# aspirin.net
KiCad netlist of a schematic drawn in EAGLE
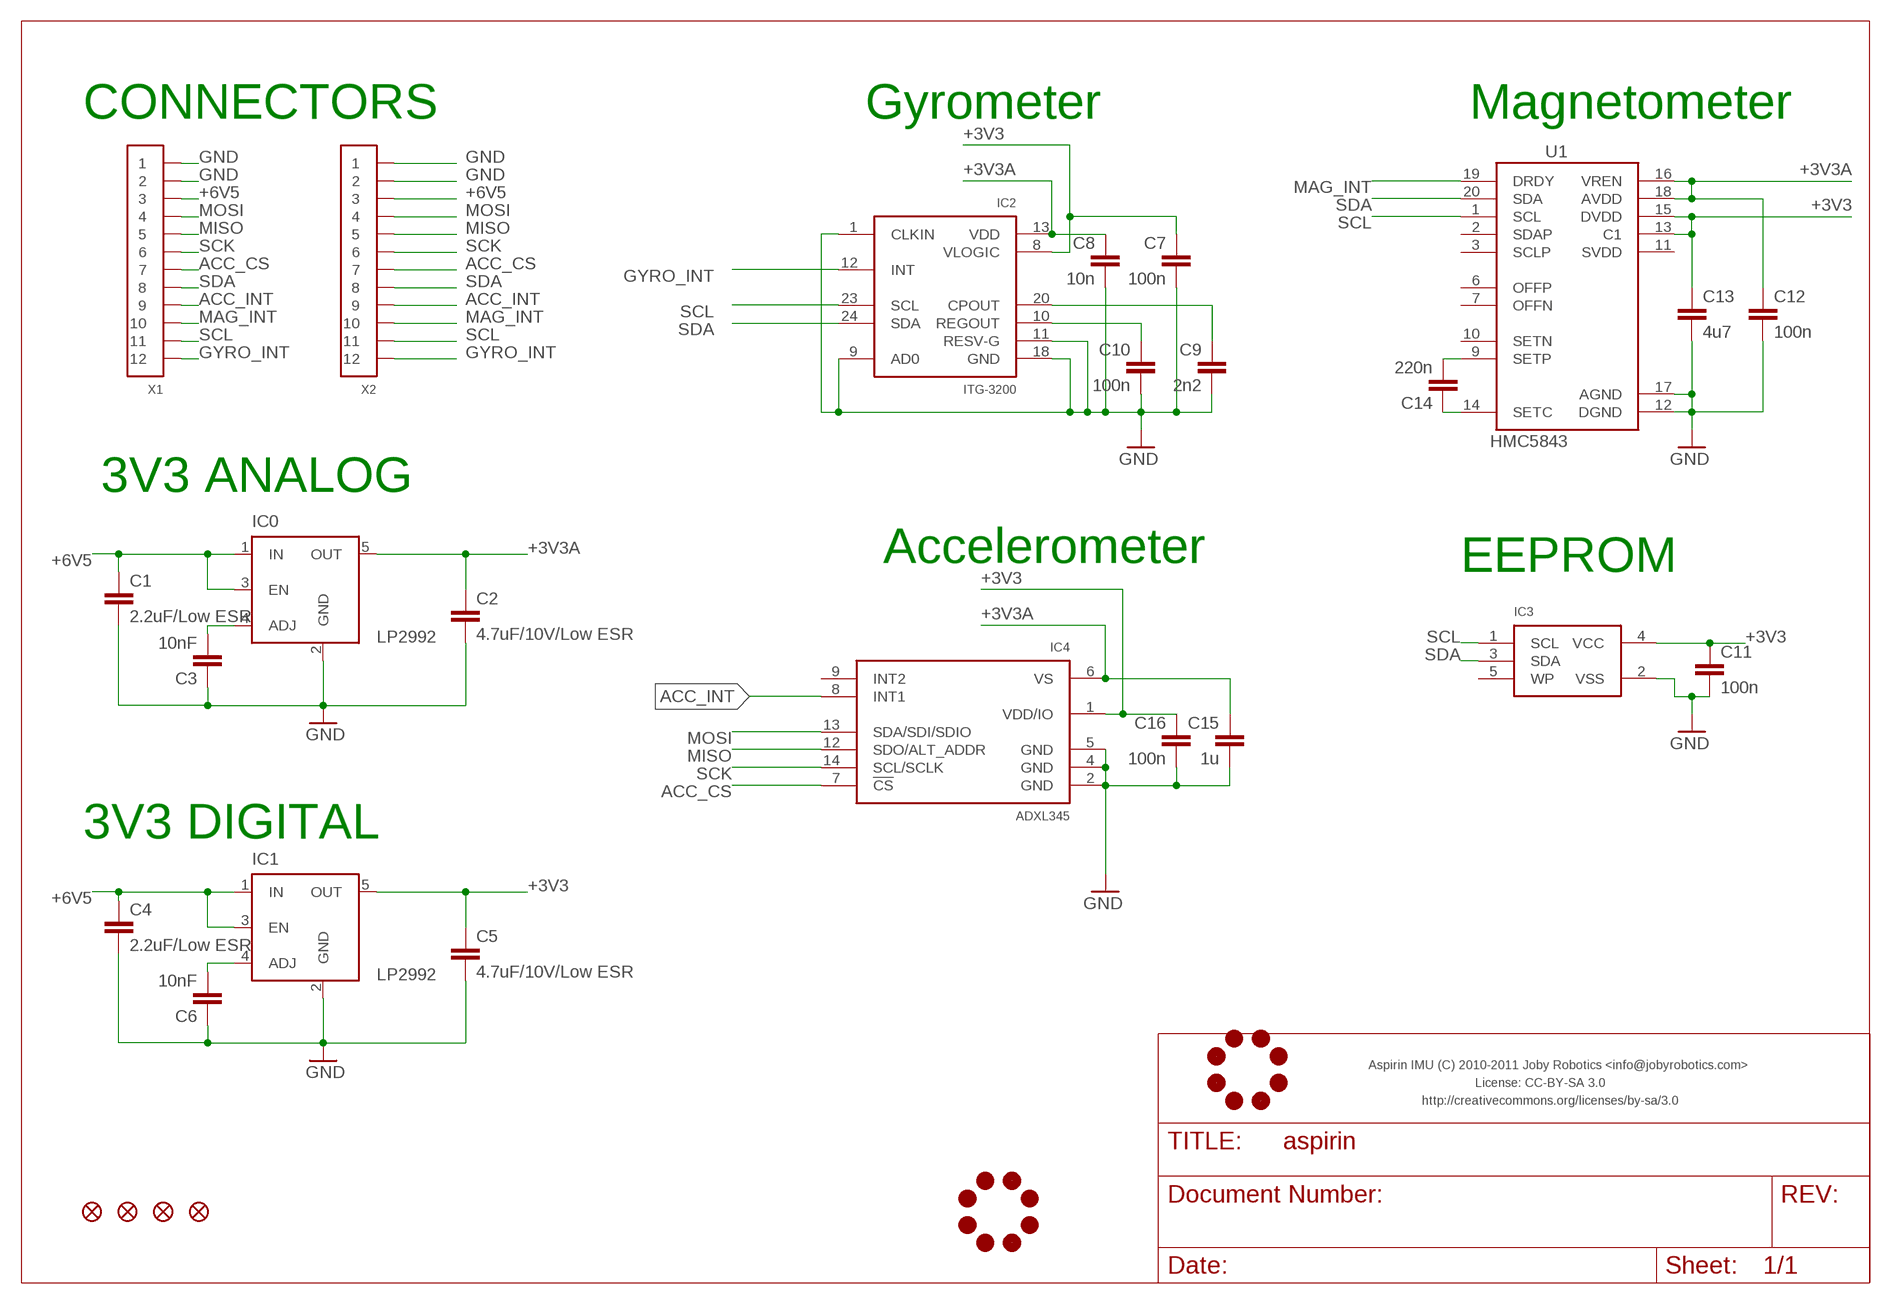
[diagram p0: schematic, sheet 1]

(export (version "E")
  (design (tool "Eeschema 10.0.6"))
  (components
    (comp (ref "C1")
      (value "2.2uF/Low ESR")
      (footprint "eagle-import:0603-CAP")
      (libsource (lib "eagle-import") (part "CAPACITOR-0603"))
    )
    (comp (ref "C2")
      (value "4.7uF/10V/Low ESR")
      (footprint "eagle-import:0603-CAP")
      (libsource (lib "eagle-import") (part "CAPACITOR-0603"))
    )
    (comp (ref "C3")
      (value "10nF")
      (footprint "eagle-import:0603-CAP")
      (libsource (lib "eagle-import") (part "CAPACITOR-0603"))
    )
    (comp (ref "C4")
      (value "2.2uF/Low ESR")
      (footprint "eagle-import:0603-CAP")
      (libsource (lib "eagle-import") (part "CAPACITOR-0603"))
    )
    (comp (ref "C5")
      (value "4.7uF/10V/Low ESR")
      (footprint "eagle-import:0603-CAP")
      (libsource (lib "eagle-import") (part "CAPACITOR-0603"))
    )
    (comp (ref "C6")
      (value "10nF")
      (footprint "eagle-import:0603-CAP")
      (libsource (lib "eagle-import") (part "CAPACITOR-0603"))
    )
    (comp (ref "C7")
      (value "100n")
      (footprint "eagle-import:0603-CAP")
      (libsource (lib "eagle-import") (part "CAPACITOR-0603"))
    )
    (comp (ref "C8")
      (value "10n")
      (footprint "eagle-import:0603-CAP")
      (libsource (lib "eagle-import") (part "CAPACITOR-0603"))
    )
    (comp (ref "C9")
      (value "2n2")
      (footprint "eagle-import:0603-CAP")
      (libsource (lib "eagle-import") (part "CAPACITOR-0603"))
    )
    (comp (ref "C10")
      (value "100n")
      (footprint "eagle-import:0603-CAP")
      (libsource (lib "eagle-import") (part "CAPACITOR-0603"))
    )
    (comp (ref "C11")
      (value "100n")
      (footprint "eagle-import:0603-CAP")
      (libsource (lib "eagle-import") (part "CAPACITOR-0603"))
    )
    (comp (ref "C12")
      (value "100n")
      (footprint "eagle-import:0603-CAP")
      (libsource (lib "eagle-import") (part "CAPACITOR-0603"))
    )
    (comp (ref "C13")
      (value "4u7")
      (footprint "eagle-import:0603-CAP")
      (libsource (lib "eagle-import") (part "CAPACITOR-0603"))
    )
    (comp (ref "C14")
      (value "220n")
      (footprint "eagle-import:0603-CAP")
      (libsource (lib "eagle-import") (part "CAPACITOR-0603"))
    )
    (comp (ref "C15")
      (value "1u")
      (footprint "eagle-import:0603-CAP")
      (libsource (lib "eagle-import") (part "CAPACITOR-0603"))
    )
    (comp (ref "C16")
      (value "100n")
      (footprint "eagle-import:0603-CAP")
      (libsource (lib "eagle-import") (part "CAPACITOR-0603"))
    )
    (comp (ref "IC0")
      (value "LP2992")
      (footprint "eagle-import:SOT23-5")
      (libsource (lib "eagle-import") (part "MIC5219BM5"))
    )
    (comp (ref "IC1")
      (value "LP2992")
      (footprint "eagle-import:SOT23-5")
      (libsource (lib "eagle-import") (part "MIC5219BM5"))
    )
    (comp (ref "IC2")
      (value "ITG-3200")
      (footprint "eagle-import:QFN24-WITH-AXES")
      (libsource (lib "eagle-import") (part "ITG-3200-AX"))
    )
    (comp (ref "IC3")
      (value "I2C_EEPROM-SOT23-5")
      (footprint "eagle-import:SOT23-5")
      (libsource (lib "eagle-import") (part "I2C_EEPROM-SOT23-5"))
    )
    (comp (ref "IC4")
      (value "ADXL345")
      (footprint "eagle-import:LGA-14")
      (libsource (lib "eagle-import") (part "ADXL345"))
    )
    (comp (ref "JL1")
      (value "JOBY_LOGO-6MIL")
      (footprint "eagle-import:JOBY_LOGO_6MIL")
      (libsource (lib "eagle-import") (part "JOBY_LOGO-6MIL"))
    )
    (comp (ref "JL2")
      (value "JOBY_LOGO-6MIL")
      (footprint "eagle-import:JOBY_LOGO_6MIL")
      (libsource (lib "eagle-import") (part "JOBY_LOGO-6MIL"))
    )
    (comp (ref "JP1")
      (value "FIDUCIAL1X2")
      (footprint "eagle-import:FIDUCIAL-1X2")
      (libsource (lib "eagle-import") (part "FIDUCIAL1X2"))
    )
    (comp (ref "JP2")
      (value "FIDUCIAL1X2")
      (footprint "eagle-import:FIDUCIAL-1X2")
      (libsource (lib "eagle-import") (part "FIDUCIAL1X2"))
    )
    (comp (ref "JP3")
      (value "FIDUCIAL1X2")
      (footprint "eagle-import:FIDUCIAL-1X2")
      (libsource (lib "eagle-import") (part "FIDUCIAL1X2"))
    )
    (comp (ref "JP4")
      (value "FIDUCIAL1X2")
      (footprint "eagle-import:FIDUCIAL-1X2")
      (libsource (lib "eagle-import") (part "FIDUCIAL1X2"))
    )
    (comp (ref "U1")
      (value "HMC5843")
      (footprint "eagle-import:LPCC20-HMC5843")
      (libsource (lib "eagle-import") (part "HMC5843"))
    )
    (comp (ref "X1")
      (value "CONN_12-1-53047")
      (footprint "eagle-import:PB-53047-12")
      (libsource (lib "eagle-import") (part "CONN_12-1-53047"))
    )
    (comp (ref "X2")
      (value "CONN_12-1-53261")
      (footprint "eagle-import:PB-53261-12")
      (libsource (lib "eagle-import") (part "CONN_12-1-53261"))
    )
  )
  (nets
    (net (code "1") (name "/+3V3") (class "Default")
      (node (ref "C11") (pin "P$1") (pinfunction "1_P$1") (pintype "passive"))
      (node (ref "C13") (pin "P$1") (pinfunction "1_P$1") (pintype "passive"))
      (node (ref "C16") (pin "P$1") (pinfunction "1_P$1") (pintype "passive"))
      (node (ref "C5") (pin "P$1") (pinfunction "1_P$1") (pintype "passive"))
      (node (ref "C7") (pin "P$1") (pinfunction "1_P$1") (pintype "passive"))
      (node (ref "IC1") (pin "5") (pinfunction "OUT_5") (pintype "output"))
      (node (ref "IC2") (pin "8") (pinfunction "VLOGIC_8") (pintype "bidirectional"))
      (node (ref "IC3") (pin "4") (pinfunction "VCC_4") (pintype "bidirectional"))
      (node (ref "IC4") (pin "1") (pinfunction "VDD/IO_1") (pintype "bidirectional"))
      (node (ref "U1") (pin "13") (pinfunction "C1_13") (pintype "bidirectional"))
      (node (ref "U1") (pin "15") (pinfunction "DVDD_15") (pintype "bidirectional"))
    )
    (net (code "2") (name "/+3V3A") (class "Default")
      (node (ref "C12") (pin "P$1") (pinfunction "1_P$1") (pintype "passive"))
      (node (ref "C15") (pin "P$1") (pinfunction "1_P$1") (pintype "passive"))
      (node (ref "C2") (pin "P$1") (pinfunction "1_P$1") (pintype "passive"))
      (node (ref "C8") (pin "P$1") (pinfunction "1_P$1") (pintype "passive"))
      (node (ref "IC0") (pin "5") (pinfunction "OUT_5") (pintype "output"))
      (node (ref "IC2") (pin "13") (pinfunction "VDD_13") (pintype "bidirectional"))
      (node (ref "IC4") (pin "6") (pinfunction "VS_6") (pintype "bidirectional"))
      (node (ref "U1") (pin "16") (pinfunction "VREN_16") (pintype "bidirectional"))
      (node (ref "U1") (pin "18") (pinfunction "AVDD_18") (pintype "bidirectional"))
    )
    (net (code "3") (name "/+6V5") (class "Default")
      (node (ref "C1") (pin "P$1") (pinfunction "1_P$1") (pintype "passive"))
      (node (ref "C4") (pin "P$1") (pinfunction "1_P$1") (pintype "passive"))
      (node (ref "IC0") (pin "1") (pinfunction "IN_1") (pintype "input"))
      (node (ref "IC0") (pin "3") (pinfunction "EN_3") (pintype "input"))
      (node (ref "IC1") (pin "1") (pinfunction "IN_1") (pintype "input"))
      (node (ref "IC1") (pin "3") (pinfunction "EN_3") (pintype "input"))
      (node (ref "X1") (pin "3") (pinfunction "3_3") (pintype "bidirectional"))
      (node (ref "X2") (pin "3") (pinfunction "3_3") (pintype "bidirectional"))
    )
    (net (code "4") (name "/ACC_CS") (class "Default")
      (node (ref "IC4") (pin "7") (pinfunction "~{CS}_7") (pintype "bidirectional"))
      (node (ref "X1") (pin "7") (pinfunction "7_7") (pintype "bidirectional"))
      (node (ref "X2") (pin "7") (pinfunction "7_7") (pintype "bidirectional"))
    )
    (net (code "5") (name "/GYRO_INT") (class "Default")
      (node (ref "IC2") (pin "12") (pinfunction "INT_12") (pintype "bidirectional"))
      (node (ref "X1") (pin "12") (pinfunction "12_12") (pintype "bidirectional"))
      (node (ref "X2") (pin "12") (pinfunction "12_12") (pintype "bidirectional"))
    )
    (net (code "6") (name "/MAG_INT") (class "Default")
      (node (ref "U1") (pin "19") (pinfunction "DRDY_19") (pintype "bidirectional"))
      (node (ref "X1") (pin "10") (pinfunction "10_10") (pintype "bidirectional"))
      (node (ref "X2") (pin "10") (pinfunction "10_10") (pintype "bidirectional"))
    )
    (net (code "7") (name "/MISO") (class "Default")
      (node (ref "IC4") (pin "12") (pinfunction "SDO/ALT_ADDR_12") (pintype "bidirectional"))
      (node (ref "X1") (pin "5") (pinfunction "5_5") (pintype "bidirectional"))
      (node (ref "X2") (pin "5") (pinfunction "5_5") (pintype "bidirectional"))
    )
    (net (code "8") (name "/MOSI") (class "Default")
      (node (ref "IC4") (pin "13") (pinfunction "SDA/SDI/SDIO_13") (pintype "bidirectional"))
      (node (ref "X1") (pin "4") (pinfunction "4_4") (pintype "bidirectional"))
      (node (ref "X2") (pin "4") (pinfunction "4_4") (pintype "bidirectional"))
    )
    (net (code "9") (name "/SCK") (class "Default")
      (node (ref "IC4") (pin "14") (pinfunction "SCL/SCLK_14") (pintype "bidirectional"))
      (node (ref "X1") (pin "6") (pinfunction "6_6") (pintype "bidirectional"))
      (node (ref "X2") (pin "6") (pinfunction "6_6") (pintype "bidirectional"))
    )
    (net (code "10") (name "/SCL") (class "Default")
      (node (ref "IC2") (pin "23") (pinfunction "SCL_23") (pintype "bidirectional"))
      (node (ref "IC3") (pin "1") (pinfunction "SCL_1") (pintype "bidirectional"))
      (node (ref "U1") (pin "1") (pinfunction "SCL_1") (pintype "bidirectional"))
      (node (ref "X1") (pin "11") (pinfunction "11_11") (pintype "bidirectional"))
      (node (ref "X2") (pin "11") (pinfunction "11_11") (pintype "bidirectional"))
    )
    (net (code "11") (name "/SDA") (class "Default")
      (node (ref "IC2") (pin "24") (pinfunction "SDA_24") (pintype "bidirectional"))
      (node (ref "IC3") (pin "3") (pinfunction "SDA_3") (pintype "bidirectional"))
      (node (ref "U1") (pin "20") (pinfunction "SDA_20") (pintype "bidirectional"))
      (node (ref "X1") (pin "8") (pinfunction "8_8") (pintype "bidirectional"))
      (node (ref "X2") (pin "8") (pinfunction "8_8") (pintype "bidirectional"))
    )
    (net (code "12") (name "ACC_INT") (class "Default")
      (node (ref "IC4") (pin "8") (pinfunction "INT1_8") (pintype "bidirectional"))
      (node (ref "X1") (pin "9") (pinfunction "9_9") (pintype "bidirectional"))
      (node (ref "X2") (pin "9") (pinfunction "9_9") (pintype "bidirectional"))
    )
    (net (code "13") (name "GND") (class "Default")
      (node (ref "C1") (pin "P$2") (pinfunction "2_P$2") (pintype "passive"))
      (node (ref "C10") (pin "P$2") (pinfunction "2_P$2") (pintype "passive"))
      (node (ref "C11") (pin "P$2") (pinfunction "2_P$2") (pintype "passive"))
      (node (ref "C12") (pin "P$2") (pinfunction "2_P$2") (pintype "passive"))
      (node (ref "C13") (pin "P$2") (pinfunction "2_P$2") (pintype "passive"))
      (node (ref "C15") (pin "P$2") (pinfunction "2_P$2") (pintype "passive"))
      (node (ref "C16") (pin "P$2") (pinfunction "2_P$2") (pintype "passive"))
      (node (ref "C2") (pin "P$2") (pinfunction "2_P$2") (pintype "passive"))
      (node (ref "C3") (pin "P$1") (pinfunction "1_P$1") (pintype "passive"))
      (node (ref "C4") (pin "P$2") (pinfunction "2_P$2") (pintype "passive"))
      (node (ref "C5") (pin "P$2") (pinfunction "2_P$2") (pintype "passive"))
      (node (ref "C6") (pin "P$1") (pinfunction "1_P$1") (pintype "passive"))
      (node (ref "C7") (pin "P$2") (pinfunction "2_P$2") (pintype "passive"))
      (node (ref "C8") (pin "P$2") (pinfunction "2_P$2") (pintype "passive"))
      (node (ref "C9") (pin "P$2") (pinfunction "2_P$2") (pintype "passive"))
      (node (ref "IC0") (pin "2") (pinfunction "GND_2") (pintype "power_in"))
      (node (ref "IC1") (pin "2") (pinfunction "GND_2") (pintype "power_in"))
      (node (ref "IC2") (pin "1") (pinfunction "CLKIN_1") (pintype "bidirectional"))
      (node (ref "IC2") (pin "11") (pinfunction "RESV-G_11") (pintype "bidirectional"))
      (node (ref "IC2") (pin "18") (pinfunction "GND_18") (pintype "bidirectional"))
      (node (ref "IC2") (pin "9") (pinfunction "AD0_9") (pintype "bidirectional"))
      (node (ref "IC3") (pin "2") (pinfunction "VSS_2") (pintype "bidirectional"))
      (node (ref "IC4") (pin "2") (pinfunction "GND_2") (pintype "bidirectional"))
      (node (ref "IC4") (pin "4") (pinfunction "GND_4") (pintype "bidirectional"))
      (node (ref "IC4") (pin "5") (pinfunction "GND_5") (pintype "bidirectional"))
      (node (ref "U1") (pin "12") (pinfunction "DGND_12") (pintype "bidirectional"))
      (node (ref "U1") (pin "17") (pinfunction "AGND_17") (pintype "bidirectional"))
      (node (ref "X1") (pin "1") (pinfunction "1_1") (pintype "bidirectional"))
      (node (ref "X1") (pin "2") (pinfunction "2_2") (pintype "bidirectional"))
      (node (ref "X2") (pin "1") (pinfunction "1_1") (pintype "bidirectional"))
      (node (ref "X2") (pin "2") (pinfunction "2_2") (pintype "bidirectional"))
    )
    (net (code "14") (name "Net-(C3-2)") (class "Default")
      (node (ref "C3") (pin "P$2") (pinfunction "2_P$2") (pintype "passive"))
      (node (ref "IC0") (pin "4") (pinfunction "ADJ_4") (pintype "passive"))
    )
    (net (code "15") (name "Net-(C6-2)") (class "Default")
      (node (ref "C6") (pin "P$2") (pinfunction "2_P$2") (pintype "passive"))
      (node (ref "IC1") (pin "4") (pinfunction "ADJ_4") (pintype "passive"))
    )
    (net (code "16") (name "Net-(C9-1)") (class "Default")
      (node (ref "C9") (pin "P$1") (pinfunction "1_P$1") (pintype "passive"))
      (node (ref "IC2") (pin "20") (pinfunction "CPOUT_20") (pintype "bidirectional"))
    )
    (net (code "17") (name "Net-(C10-1)") (class "Default")
      (node (ref "C10") (pin "P$1") (pinfunction "1_P$1") (pintype "passive"))
      (node (ref "IC2") (pin "10") (pinfunction "REGOUT_10") (pintype "bidirectional"))
    )
    (net (code "18") (name "Net-(C14-1)") (class "Default")
      (node (ref "C14") (pin "P$1") (pinfunction "1_P$1") (pintype "passive"))
      (node (ref "U1") (pin "14") (pinfunction "SETC_14") (pintype "bidirectional"))
    )
    (net (code "19") (name "Net-(C14-2)") (class "Default")
      (node (ref "C14") (pin "P$2") (pinfunction "2_P$2") (pintype "passive"))
      (node (ref "U1") (pin "9") (pinfunction "SETP_9") (pintype "bidirectional"))
    )
    (net (code "20") (name "unconnected-(IC3-WP-Pad5)") (class "Default")
      (node (ref "IC3") (pin "5") (pinfunction "WP_5") (pintype "bidirectional"))
    )
    (net (code "21") (name "unconnected-(IC4-INT2-Pad9)") (class "Default")
      (node (ref "IC4") (pin "9") (pinfunction "INT2_9") (pintype "bidirectional"))
    )
    (net (code "22") (name "unconnected-(U1-OFFN-Pad7)") (class "Default")
      (node (ref "U1") (pin "7") (pinfunction "OFFN_7") (pintype "bidirectional"))
    )
    (net (code "23") (name "unconnected-(U1-OFFP-Pad6)") (class "Default")
      (node (ref "U1") (pin "6") (pinfunction "OFFP_6") (pintype "bidirectional"))
    )
    (net (code "24") (name "unconnected-(U1-SCLP-Pad3)") (class "Default")
      (node (ref "U1") (pin "3") (pinfunction "SCLP_3") (pintype "bidirectional"))
    )
    (net (code "25") (name "unconnected-(U1-SDAP-Pad2)") (class "Default")
      (node (ref "U1") (pin "2") (pinfunction "SDAP_2") (pintype "bidirectional"))
    )
    (net (code "26") (name "unconnected-(U1-SETN-Pad10)") (class "Default")
      (node (ref "U1") (pin "10") (pinfunction "SETN_10") (pintype "bidirectional"))
    )
    (net (code "27") (name "unconnected-(U1-SVDD-Pad11)") (class "Default")
      (node (ref "U1") (pin "11") (pinfunction "SVDD_11") (pintype "bidirectional"))
    )
  )
)
